# Cradle_Controller.net
KiCad netlist of a schematic drawn in Altium Designer
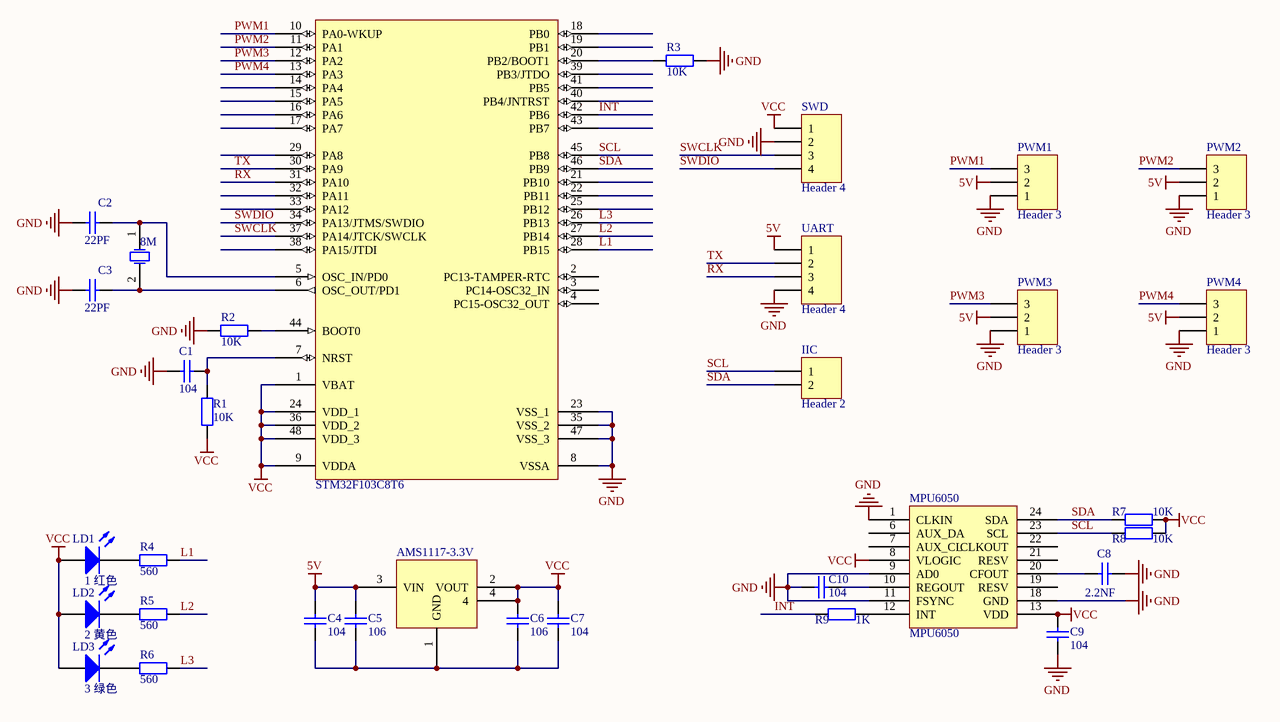
[diagram p0: Cradle Controller.SchDoc]

(export (version "E")
  (design (tool "Eeschema 10.0.6"))
  (components
    (comp (ref "8M")
      (value "8M")
      (footprint "SOP10")
      (description "Crystal Oscillator")
      (fields (field (name "PUBLISHER") "Altium Limited"))
      (libsource (lib "FlyWay_Prj") (part "XTAL"))
    )
    (comp (ref "AMS1117-3.3V")
      (value "AMS1117-3.3V")
      (footprint "SOT223_M")
      (libsource (lib "1117-3.3V") (part "1117-3.3V"))
    )
    (comp (ref "C1")
      (value "104")
      (footprint "C0805")
      (description "Capacitor")
      (fields (field (name "PUBLISHER") "Altium Limited"))
      (libsource (lib "FlyWay_Prj") (part "Cap"))
    )
    (comp (ref "C2")
      (value "22PF")
      (footprint "C0805")
      (description "Capacitor")
      (fields (field (name "PUBLISHER") "Altium Limited"))
      (libsource (lib "FlyWay_Prj") (part "Cap"))
    )
    (comp (ref "C3")
      (value "22PF")
      (footprint "C0805")
      (description "Capacitor")
      (fields (field (name "Comment") "20PF") (field (name "PUBLISHER") "Altium Limited"))
      (libsource (lib "FlyWay_Prj") (part "Cap"))
    )
    (comp (ref "C4")
      (value "104")
      (footprint "C0805")
      (description "Capacitor (Semiconductor SIM Model)")
      (fields (field (name "PUBLISHER") "Altium Limited"))
      (libsource (lib "Miscellaneous Devices") (part "Cap Semi"))
    )
    (comp (ref "C5")
      (value "106")
      (footprint "C0805")
      (description "Capacitor (Semiconductor SIM Model)")
      (fields (field (name "PUBLISHER") "Altium Limited"))
      (libsource (lib "Miscellaneous Devices") (part "Cap Semi"))
    )
    (comp (ref "C6")
      (value "106")
      (footprint "C0805")
      (description "Capacitor (Semiconductor SIM Model)")
      (fields (field (name "PUBLISHER") "Altium Limited"))
      (libsource (lib "Miscellaneous Devices") (part "Cap Semi"))
    )
    (comp (ref "C7")
      (value "104")
      (footprint "C0805")
      (description "Capacitor (Semiconductor SIM Model)")
      (fields (field (name "PUBLISHER") "Altium Limited"))
      (libsource (lib "Miscellaneous Devices") (part "Cap Semi"))
    )
    (comp (ref "C8")
      (value "2.2NF")
      (footprint "C0805")
      (description "Capacitor")
      (fields (field (name "PUBLISHER") "Altium Limited"))
      (libsource (lib "FlyWay_Prj") (part "Cap"))
    )
    (comp (ref "C9")
      (value "104")
      (footprint "C0805")
      (description "Capacitor")
      (fields (field (name "PUBLISHER") "Altium Limited"))
      (libsource (lib "FlyWay_Prj") (part "Cap"))
    )
    (comp (ref "C10")
      (value "104")
      (footprint "C0805")
      (description "Capacitor")
      (fields (field (name "PUBLISHER") "Altium Limited"))
      (libsource (lib "FlyWay_Prj") (part "Cap"))
    )
    (comp (ref "IIC")
      (value "Header 2")
      (footprint "HDR1X2")
      (description "Header, 2-Pin")
      (fields (field (name "PUBLISHER") "Altium Limited"))
      (libsource (lib "FlyWay_Prj") (part "Header 2"))
    )
    (comp (ref "LD1")
      (value "1 红色")
      (footprint "3.5X2.8X1.9")
      (description "Typical BLUE SiC LED")
      (fields (field (name "PUBLISHER") "Altium Limited"))
      (libsource (lib "Miscellaneous Devices") (part "LED3"))
    )
    (comp (ref "LD2")
      (value "2 黄色")
      (footprint "3.5X2.8X1.9")
      (description "Typical BLUE SiC LED")
      (fields (field (name "PUBLISHER") "Altium Limited"))
      (libsource (lib "Miscellaneous Devices") (part "LED3"))
    )
    (comp (ref "LD3")
      (value "3 绿色")
      (footprint "3.5X2.8X1.9")
      (description "Typical BLUE SiC LED")
      (fields (field (name "PUBLISHER") "Altium Limited"))
      (libsource (lib "Miscellaneous Devices") (part "LED3"))
    )
    (comp (ref "MPU6050")
      (value "MPU6050")
      (footprint "MPU6050")
      (libsource (lib "FlyWay_Prj") (part "MPU6050"))
    )
    (comp (ref "PWM1")
      (value "Header 3")
      (footprint "HDR1X3")
      (description "Header, 3-Pin")
      (fields (field (name "PUBLISHER") "Altium Limited"))
      (libsource (lib "FlyWay_Prj") (part "Header 3"))
    )
    (comp (ref "PWM2")
      (value "Header 3")
      (footprint "HDR1X3")
      (description "Header, 3-Pin")
      (fields (field (name "PUBLISHER") "Altium Limited"))
      (libsource (lib "FlyWay_Prj") (part "Header 3"))
    )
    (comp (ref "PWM3")
      (value "Header 3")
      (footprint "HDR1X3")
      (description "Header, 3-Pin")
      (fields (field (name "PUBLISHER") "Altium Limited"))
      (libsource (lib "FlyWay_Prj") (part "Header 3"))
    )
    (comp (ref "PWM4")
      (value "Header 3")
      (footprint "HDR1X3")
      (description "Header, 3-Pin")
      (fields (field (name "PUBLISHER") "Altium Limited"))
      (libsource (lib "FlyWay_Prj") (part "Header 3"))
    )
    (comp (ref "R1")
      (value "10K")
      (footprint "6-0805_M")
      (description "Resistor")
      (fields (field (name "PUBLISHER") "Altium Limited"))
      (libsource (lib "") (part "Res2_1"))
    )
    (comp (ref "R2")
      (value "10K")
      (footprint "6-0805_M")
      (description "Resistor")
      (fields (field (name "PUBLISHER") "Altium Limited"))
      (libsource (lib "FlyWay_Prj") (part "Res2"))
    )
    (comp (ref "R3")
      (value "10K")
      (footprint "6-0805_M")
      (description "Resistor")
      (fields (field (name "PUBLISHER") "Altium Limited"))
      (libsource (lib "FlyWay_Prj") (part "Res2"))
    )
    (comp (ref "R4")
      (value "560")
      (footprint "6-0805_M")
      (description "Resistor")
      (fields (field (name "PUBLISHER") "Altium Limited"))
      (libsource (lib "Miscellaneous Devices") (part "Res2"))
    )
    (comp (ref "R5")
      (value "560")
      (footprint "6-0805_M")
      (description "Resistor")
      (fields (field (name "PUBLISHER") "Altium Limited"))
      (libsource (lib "Miscellaneous Devices") (part "Res2"))
    )
    (comp (ref "R6")
      (value "560")
      (footprint "6-0805_M")
      (description "Resistor")
      (fields (field (name "PUBLISHER") "Altium Limited"))
      (libsource (lib "Miscellaneous Devices") (part "Res2"))
    )
    (comp (ref "R7")
      (value "10K")
      (footprint "6-0805_M")
      (description "Resistor")
      (fields (field (name "PUBLISHER") "Altium Limited"))
      (libsource (lib "FlyWay_Prj") (part "Res2"))
    )
    (comp (ref "R8")
      (value "10K")
      (footprint "6-0805_M")
      (description "Resistor")
      (fields (field (name "PUBLISHER") "Altium Limited"))
      (libsource (lib "FlyWay_Prj") (part "Res2"))
    )
    (comp (ref "R9")
      (value "1K")
      (footprint "6-0805_M")
      (description "Resistor")
      (fields (field (name "PUBLISHER") "Altium Limited"))
      (libsource (lib "FlyWay_Prj") (part "Res2"))
    )
    (comp (ref "STM32F103C8T6")
      (value "STM32F103C8T6")
      (footprint "LQFP48_N")
      (description "STM32 ARM-based 32-bit MCU with 64 Kbytes Flash, 48-pin LQFP, Industrial Temperature")
      (fields (field (name "PUBLISHER") "Altium Limited"))
      (libsource (lib "ST Microcontroller 32-Bit STM32") (part "STM32F103C8T6"))
    )
    (comp (ref "SWD")
      (value "Header 4")
      (footprint "HDR1X4")
      (description "Header, 4-Pin")
      (fields (field (name "PUBLISHER") "Altium Limited"))
      (libsource (lib "FlyWay_Prj") (part "Header 4"))
    )
    (comp (ref "UART")
      (value "Header 4")
      (footprint "HDR1X4")
      (description "Header, 4-Pin")
      (fields (field (name "PUBLISHER") "Altium Limited"))
      (libsource (lib "FlyWay_Prj") (part "Header 4"))
    )
  )
  (nets
    (net (code "1") (name "/INT") (class "Default")
      (node (ref "R9") (pin "1") (pinfunction "1_1") (pintype "passive"))
      (node (ref "STM32F103C8T6") (pin "42") (pinfunction "PB6_42") (pintype "bidirectional"))
    )
    (net (code "2") (name "/L1") (class "Default")
      (node (ref "R4") (pin "1") (pinfunction "1_1") (pintype "passive"))
      (node (ref "STM32F103C8T6") (pin "28") (pinfunction "PB15_28") (pintype "bidirectional"))
    )
    (net (code "3") (name "/L2") (class "Default")
      (node (ref "R5") (pin "1") (pinfunction "1_1") (pintype "passive"))
      (node (ref "STM32F103C8T6") (pin "27") (pinfunction "PB14_27") (pintype "bidirectional"))
    )
    (net (code "4") (name "/L3") (class "Default")
      (node (ref "R6") (pin "1") (pinfunction "1_1") (pintype "passive"))
      (node (ref "STM32F103C8T6") (pin "26") (pinfunction "PB13_26") (pintype "bidirectional"))
    )
    (net (code "5") (name "/PWM1") (class "Default")
      (node (ref "PWM1") (pin "3") (pinfunction "3_3") (pintype "passive"))
      (node (ref "STM32F103C8T6") (pin "10") (pinfunction "PA0-WKUP_10") (pintype "bidirectional"))
    )
    (net (code "6") (name "/PWM2") (class "Default")
      (node (ref "PWM2") (pin "3") (pinfunction "3_3") (pintype "passive"))
      (node (ref "STM32F103C8T6") (pin "11") (pinfunction "PA1_11") (pintype "bidirectional"))
    )
    (net (code "7") (name "/PWM3") (class "Default")
      (node (ref "PWM3") (pin "3") (pinfunction "3_3") (pintype "passive"))
      (node (ref "STM32F103C8T6") (pin "12") (pinfunction "PA2_12") (pintype "bidirectional"))
    )
    (net (code "8") (name "/PWM4") (class "Default")
      (node (ref "PWM4") (pin "3") (pinfunction "3_3") (pintype "passive"))
      (node (ref "STM32F103C8T6") (pin "13") (pinfunction "PA3_13") (pintype "bidirectional"))
    )
    (net (code "9") (name "/RX") (class "Default")
      (node (ref "STM32F103C8T6") (pin "31") (pinfunction "PA10_31") (pintype "bidirectional"))
      (node (ref "UART") (pin "3") (pinfunction "3_3") (pintype "passive"))
    )
    (net (code "10") (name "/SCL") (class "Default")
      (node (ref "IIC") (pin "1") (pinfunction "1_1") (pintype "passive"))
      (node (ref "MPU6050") (pin "23") (pinfunction "SCL_23") (pintype "passive"))
      (node (ref "R8") (pin "1") (pinfunction "1_1") (pintype "passive"))
      (node (ref "STM32F103C8T6") (pin "45") (pinfunction "PB8_45") (pintype "bidirectional"))
    )
    (net (code "11") (name "/SDA") (class "Default")
      (node (ref "IIC") (pin "2") (pinfunction "2_2") (pintype "passive"))
      (node (ref "MPU6050") (pin "24") (pinfunction "SDA_24") (pintype "passive"))
      (node (ref "R7") (pin "1") (pinfunction "1_1") (pintype "passive"))
      (node (ref "STM32F103C8T6") (pin "46") (pinfunction "PB9_46") (pintype "bidirectional"))
    )
    (net (code "12") (name "/SWCLK") (class "Default")
      (node (ref "STM32F103C8T6") (pin "37") (pinfunction "PA14/JTCK/SWCLK_37") (pintype "bidirectional"))
      (node (ref "SWD") (pin "3") (pinfunction "3_3") (pintype "passive"))
    )
    (net (code "13") (name "/SWDIO") (class "Default")
      (node (ref "STM32F103C8T6") (pin "34") (pinfunction "PA13/JTMS/SWDIO_34") (pintype "bidirectional"))
      (node (ref "SWD") (pin "4") (pinfunction "4_4") (pintype "passive"))
    )
    (net (code "14") (name "/TX") (class "Default")
      (node (ref "STM32F103C8T6") (pin "30") (pinfunction "PA9_30") (pintype "bidirectional"))
      (node (ref "UART") (pin "2") (pinfunction "2_2") (pintype "passive"))
    )
    (net (code "15") (name "5V") (class "Default")
      (node (ref "AMS1117-3.3V") (pin "3") (pinfunction "VIN_3") (pintype "passive"))
      (node (ref "C4") (pin "1") (pinfunction "1_1") (pintype "passive"))
      (node (ref "C5") (pin "1") (pinfunction "1_1") (pintype "passive"))
      (node (ref "PWM1") (pin "2") (pinfunction "2_2") (pintype "passive"))
      (node (ref "PWM2") (pin "2") (pinfunction "2_2") (pintype "passive"))
      (node (ref "PWM3") (pin "2") (pinfunction "2_2") (pintype "passive"))
      (node (ref "PWM4") (pin "2") (pinfunction "2_2") (pintype "passive"))
      (node (ref "UART") (pin "1") (pinfunction "1_1") (pintype "passive"))
    )
    (net (code "16") (name "GND") (class "Default")
      (node (ref "C1") (pin "1") (pinfunction "1_1") (pintype "passive"))
      (node (ref "C10") (pin "1") (pinfunction "1_1") (pintype "passive"))
      (node (ref "C2") (pin "1") (pinfunction "1_1") (pintype "passive"))
      (node (ref "C3") (pin "1") (pinfunction "1_1") (pintype "passive"))
      (node (ref "C8") (pin "2") (pinfunction "2_2") (pintype "passive"))
      (node (ref "C9") (pin "1") (pinfunction "1_1") (pintype "passive"))
      (node (ref "MPU6050") (pin "1") (pinfunction "CLKIN_1") (pintype "passive"))
      (node (ref "MPU6050") (pin "11") (pinfunction "FSYNC_11") (pintype "passive"))
      (node (ref "MPU6050") (pin "18") (pinfunction "GND_18") (pintype "passive"))
      (node (ref "MPU6050") (pin "9") (pinfunction "AD0_9") (pintype "passive"))
      (node (ref "PWM1") (pin "1") (pinfunction "1_1") (pintype "passive"))
      (node (ref "PWM2") (pin "1") (pinfunction "1_1") (pintype "passive"))
      (node (ref "PWM3") (pin "1") (pinfunction "1_1") (pintype "passive"))
      (node (ref "PWM4") (pin "1") (pinfunction "1_1") (pintype "passive"))
      (node (ref "R2") (pin "1") (pinfunction "1_1") (pintype "passive"))
      (node (ref "R3") (pin "2") (pinfunction "2_2") (pintype "passive"))
      (node (ref "STM32F103C8T6") (pin "23") (pinfunction "VSS_1_23") (pintype "power_in"))
      (node (ref "STM32F103C8T6") (pin "35") (pinfunction "VSS_2_35") (pintype "power_in"))
      (node (ref "STM32F103C8T6") (pin "47") (pinfunction "VSS_3_47") (pintype "power_in"))
      (node (ref "STM32F103C8T6") (pin "8") (pinfunction "VSSA_8") (pintype "power_in"))
      (node (ref "SWD") (pin "2") (pinfunction "2_2") (pintype "passive"))
      (node (ref "UART") (pin "4") (pinfunction "4_4") (pintype "passive"))
    )
    (net (code "17") (name "Net-(8M-OSC1)") (class "Default")
      (node (ref "8M") (pin "1") (pinfunction "OSC1_1") (pintype "passive"))
      (node (ref "C2") (pin "2") (pinfunction "2_2") (pintype "passive"))
      (node (ref "STM32F103C8T6") (pin "5") (pinfunction "OSC_IN/PD0_5") (pintype "input"))
    )
    (net (code "18") (name "Net-(8M-OSC2)") (class "Default")
      (node (ref "8M") (pin "2") (pinfunction "OSC2_2") (pintype "passive"))
      (node (ref "C3") (pin "2") (pinfunction "2_2") (pintype "passive"))
      (node (ref "STM32F103C8T6") (pin "6") (pinfunction "OSC_OUT/PD1_6") (pintype "output"))
    )
    (net (code "19") (name "Net-(AMS1117-3.3V-GND)") (class "Default")
      (node (ref "AMS1117-3.3V") (pin "1") (pinfunction "GND_1") (pintype "passive"))
      (node (ref "C4") (pin "2") (pinfunction "2_2") (pintype "passive"))
      (node (ref "C5") (pin "2") (pinfunction "2_2") (pintype "passive"))
      (node (ref "C6") (pin "2") (pinfunction "2_2") (pintype "passive"))
      (node (ref "C7") (pin "2") (pinfunction "2_2") (pintype "passive"))
    )
    (net (code "20") (name "Net-(LD1-K)") (class "Default")
      (node (ref "LD1") (pin "2") (pinfunction "K_2") (pintype "passive"))
      (node (ref "R4") (pin "2") (pinfunction "2_2") (pintype "passive"))
    )
    (net (code "21") (name "Net-(LD2-K)") (class "Default")
      (node (ref "LD2") (pin "2") (pinfunction "K_2") (pintype "passive"))
      (node (ref "R5") (pin "2") (pinfunction "2_2") (pintype "passive"))
    )
    (net (code "22") (name "Net-(LD3-K)") (class "Default")
      (node (ref "LD3") (pin "2") (pinfunction "K_2") (pintype "passive"))
      (node (ref "R6") (pin "2") (pinfunction "2_2") (pintype "passive"))
    )
    (net (code "23") (name "Net-(MPU6050-CFOUT)") (class "Default")
      (node (ref "C8") (pin "1") (pinfunction "1_1") (pintype "passive"))
      (node (ref "MPU6050") (pin "20") (pinfunction "CFOUT_20") (pintype "passive"))
    )
    (net (code "24") (name "Net-(MPU6050-INT)") (class "Default")
      (node (ref "MPU6050") (pin "12") (pinfunction "INT_12") (pintype "passive"))
      (node (ref "R9") (pin "2") (pinfunction "2_2") (pintype "passive"))
    )
    (net (code "25") (name "Net-(MPU6050-REGOUT)") (class "Default")
      (node (ref "C10") (pin "2") (pinfunction "2_2") (pintype "passive"))
      (node (ref "MPU6050") (pin "10") (pinfunction "REGOUT_10") (pintype "passive"))
    )
    (net (code "26") (name "Net-(STM32F103C8T6-BOOT0)") (class "Default")
      (node (ref "R2") (pin "2") (pinfunction "2_2") (pintype "passive"))
      (node (ref "STM32F103C8T6") (pin "44") (pinfunction "BOOT0_44") (pintype "input"))
    )
    (net (code "27") (name "Net-(STM32F103C8T6-NRST)") (class "Default")
      (node (ref "C1") (pin "2") (pinfunction "2_2") (pintype "passive"))
      (node (ref "R1") (pin "2") (pinfunction "2_2") (pintype "passive"))
      (node (ref "STM32F103C8T6") (pin "7") (pinfunction "NRST_7") (pintype "bidirectional"))
    )
    (net (code "28") (name "Net-(STM32F103C8T6-PB2{slash}BOOT1)") (class "Default")
      (node (ref "R3") (pin "1") (pinfunction "1_1") (pintype "passive"))
      (node (ref "STM32F103C8T6") (pin "20") (pinfunction "PB2/BOOT1_20") (pintype "bidirectional"))
    )
    (net (code "29") (name "VCC") (class "Default")
      (node (ref "AMS1117-3.3V") (pin "2") (pinfunction "VOUT_2") (pintype "passive"))
      (node (ref "AMS1117-3.3V") (pin "4") (pinfunction "4_4") (pintype "passive"))
      (node (ref "C6") (pin "1") (pinfunction "1_1") (pintype "passive"))
      (node (ref "C7") (pin "1") (pinfunction "1_1") (pintype "passive"))
      (node (ref "C9") (pin "2") (pinfunction "2_2") (pintype "passive"))
      (node (ref "LD1") (pin "1") (pinfunction "A_1") (pintype "passive"))
      (node (ref "LD2") (pin "1") (pinfunction "A_1") (pintype "passive"))
      (node (ref "LD3") (pin "1") (pinfunction "A_1") (pintype "passive"))
      (node (ref "MPU6050") (pin "13") (pinfunction "VDD_13") (pintype "passive"))
      (node (ref "MPU6050") (pin "8") (pinfunction "VLOGIC_8") (pintype "passive"))
      (node (ref "R1") (pin "1") (pinfunction "1_1") (pintype "passive"))
      (node (ref "R7") (pin "2") (pinfunction "2_2") (pintype "passive"))
      (node (ref "R8") (pin "2") (pinfunction "2_2") (pintype "passive"))
      (node (ref "STM32F103C8T6") (pin "1") (pinfunction "VBAT_1") (pintype "power_in"))
      (node (ref "STM32F103C8T6") (pin "24") (pinfunction "VDD_1_24") (pintype "power_in"))
      (node (ref "STM32F103C8T6") (pin "36") (pinfunction "VDD_2_36") (pintype "power_in"))
      (node (ref "STM32F103C8T6") (pin "48") (pinfunction "VDD_3_48") (pintype "power_in"))
      (node (ref "STM32F103C8T6") (pin "9") (pinfunction "VDDA_9") (pintype "power_in"))
      (node (ref "SWD") (pin "1") (pinfunction "1_1") (pintype "passive"))
    )
    (net (code "30") (name "unconnected-(MPU6050-AUX_CL-Pad7)") (class "Default")
      (node (ref "MPU6050") (pin "7") (pinfunction "AUX_CL_7") (pintype "passive"))
    )
    (net (code "31") (name "unconnected-(MPU6050-AUX_DA-Pad6)") (class "Default")
      (node (ref "MPU6050") (pin "6") (pinfunction "AUX_DA_6") (pintype "passive"))
    )
    (net (code "32") (name "unconnected-(MPU6050-CLKOUT-Pad22)") (class "Default")
      (node (ref "MPU6050") (pin "22") (pinfunction "CLKOUT_22") (pintype "passive"))
    )
    (net (code "33") (name "unconnected-(MPU6050-RESV-Pad19)") (class "Default")
      (node (ref "MPU6050") (pin "19") (pinfunction "RESV_19") (pintype "passive"))
    )
    (net (code "34") (name "unconnected-(MPU6050-RESV-Pad21)") (class "Default")
      (node (ref "MPU6050") (pin "21") (pinfunction "RESV_21") (pintype "passive"))
    )
    (net (code "35") (name "unconnected-(STM32F103C8T6-PA4-Pad14)") (class "Default")
      (node (ref "STM32F103C8T6") (pin "14") (pinfunction "PA4_14") (pintype "bidirectional"))
    )
    (net (code "36") (name "unconnected-(STM32F103C8T6-PA5-Pad15)") (class "Default")
      (node (ref "STM32F103C8T6") (pin "15") (pinfunction "PA5_15") (pintype "bidirectional"))
    )
    (net (code "37") (name "unconnected-(STM32F103C8T6-PA6-Pad16)") (class "Default")
      (node (ref "STM32F103C8T6") (pin "16") (pinfunction "PA6_16") (pintype "bidirectional"))
    )
    (net (code "38") (name "unconnected-(STM32F103C8T6-PA7-Pad17)") (class "Default")
      (node (ref "STM32F103C8T6") (pin "17") (pinfunction "PA7_17") (pintype "bidirectional"))
    )
    (net (code "39") (name "unconnected-(STM32F103C8T6-PA8-Pad29)") (class "Default")
      (node (ref "STM32F103C8T6") (pin "29") (pinfunction "PA8_29") (pintype "bidirectional"))
    )
    (net (code "40") (name "unconnected-(STM32F103C8T6-PA11-Pad32)") (class "Default")
      (node (ref "STM32F103C8T6") (pin "32") (pinfunction "PA11_32") (pintype "bidirectional"))
    )
    (net (code "41") (name "unconnected-(STM32F103C8T6-PA12-Pad33)") (class "Default")
      (node (ref "STM32F103C8T6") (pin "33") (pinfunction "PA12_33") (pintype "bidirectional"))
    )
    (net (code "42") (name "unconnected-(STM32F103C8T6-PA15{slash}JTDI-Pad38)") (class "Default")
      (node (ref "STM32F103C8T6") (pin "38") (pinfunction "PA15/JTDI_38") (pintype "bidirectional"))
    )
    (net (code "43") (name "unconnected-(STM32F103C8T6-PB0-Pad18)") (class "Default")
      (node (ref "STM32F103C8T6") (pin "18") (pinfunction "PB0_18") (pintype "bidirectional"))
    )
    (net (code "44") (name "unconnected-(STM32F103C8T6-PB1-Pad19)") (class "Default")
      (node (ref "STM32F103C8T6") (pin "19") (pinfunction "PB1_19") (pintype "bidirectional"))
    )
    (net (code "45") (name "unconnected-(STM32F103C8T6-PB3{slash}JTDO-Pad39)") (class "Default")
      (node (ref "STM32F103C8T6") (pin "39") (pinfunction "PB3/JTDO_39") (pintype "bidirectional"))
    )
    (net (code "46") (name "unconnected-(STM32F103C8T6-PB4{slash}JNTRST-Pad40)") (class "Default")
      (node (ref "STM32F103C8T6") (pin "40") (pinfunction "PB4/JNTRST_40") (pintype "bidirectional"))
    )
    (net (code "47") (name "unconnected-(STM32F103C8T6-PB5-Pad41)") (class "Default")
      (node (ref "STM32F103C8T6") (pin "41") (pinfunction "PB5_41") (pintype "bidirectional"))
    )
    (net (code "48") (name "unconnected-(STM32F103C8T6-PB7-Pad43)") (class "Default")
      (node (ref "STM32F103C8T6") (pin "43") (pinfunction "PB7_43") (pintype "bidirectional"))
    )
    (net (code "49") (name "unconnected-(STM32F103C8T6-PB10-Pad21)") (class "Default")
      (node (ref "STM32F103C8T6") (pin "21") (pinfunction "PB10_21") (pintype "bidirectional"))
    )
    (net (code "50") (name "unconnected-(STM32F103C8T6-PB11-Pad22)") (class "Default")
      (node (ref "STM32F103C8T6") (pin "22") (pinfunction "PB11_22") (pintype "bidirectional"))
    )
    (net (code "51") (name "unconnected-(STM32F103C8T6-PB12-Pad25)") (class "Default")
      (node (ref "STM32F103C8T6") (pin "25") (pinfunction "PB12_25") (pintype "bidirectional"))
    )
    (net (code "52") (name "unconnected-(STM32F103C8T6-PC13-TAMPER-RTC-Pad2)") (class "Default")
      (node (ref "STM32F103C8T6") (pin "2") (pinfunction "PC13-TAMPER-RTC_2") (pintype "bidirectional"))
    )
    (net (code "53") (name "unconnected-(STM32F103C8T6-PC14-OSC32_IN-Pad3)") (class "Default")
      (node (ref "STM32F103C8T6") (pin "3") (pinfunction "PC14-OSC32_IN_3") (pintype "bidirectional"))
    )
    (net (code "54") (name "unconnected-(STM32F103C8T6-PC15-OSC32_OUT-Pad4)") (class "Default")
      (node (ref "STM32F103C8T6") (pin "4") (pinfunction "PC15-OSC32_OUT_4") (pintype "bidirectional"))
    )
  )
)
